# avr-remocon.net
KiCad netlist of a schematic drawn in EAGLE
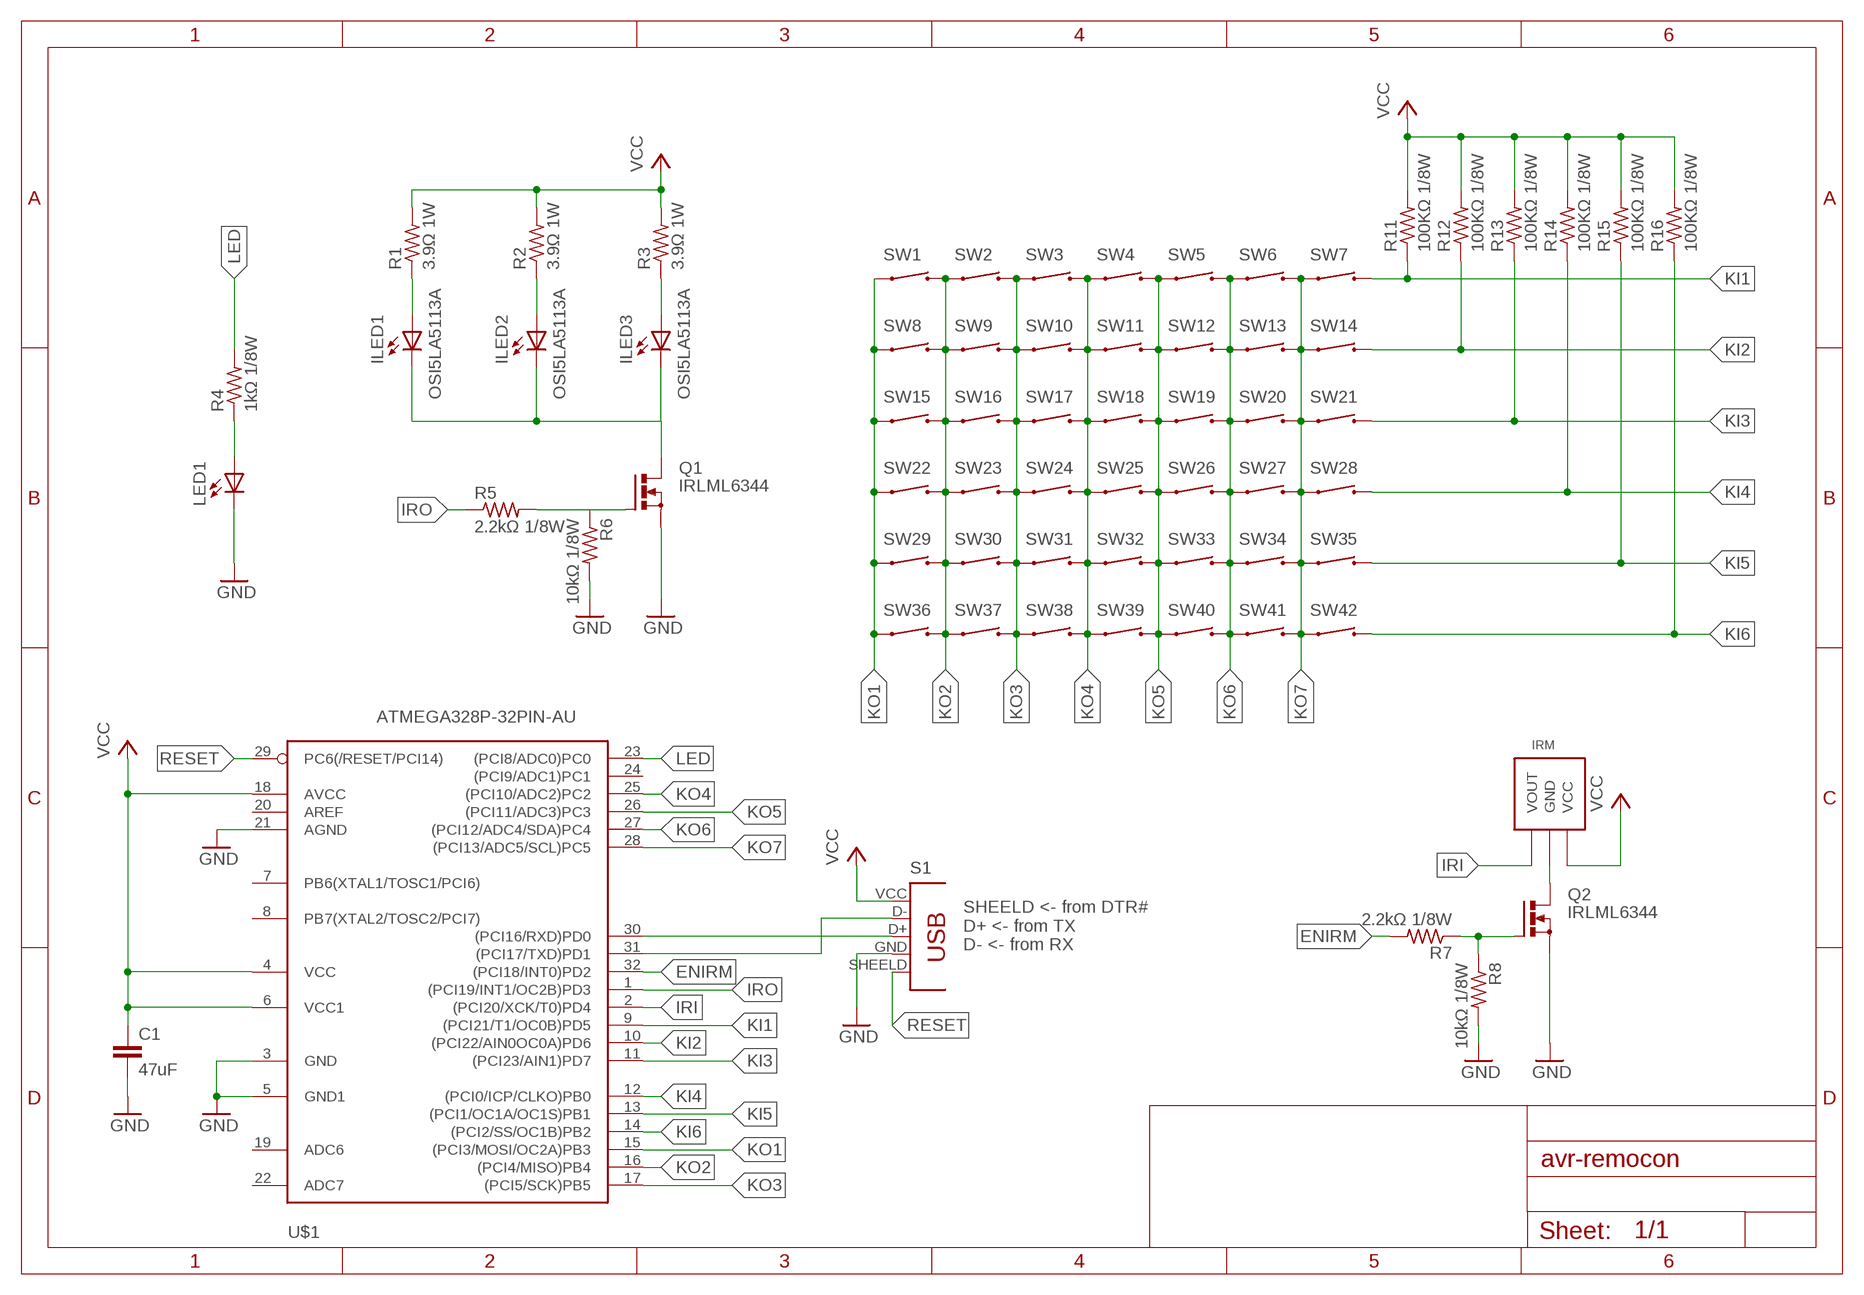
[diagram p0: schematic, sheet 1]

(export (version "E")
  (design (tool "Eeschema 10.0.6"))
  (components
    (comp (ref "C1")
      (value "47uF")
      (footprint "eagle-import:C3216")
      (libsource (lib "eagle-import") (part "C-EUC3216"))
    )
    (comp (ref "ILED1")
      (value "OSI5LA5113A")
      (footprint "eagle-import:LED5MM-SIDE-DOWN3")
      (libsource (lib "eagle-import") (part "LED-SIDEDOWN3"))
    )
    (comp (ref "ILED2")
      (value "OSI5LA5113A")
      (footprint "eagle-import:LED5MM-SIDE-DOWN3")
      (libsource (lib "eagle-import") (part "LED-SIDEDOWN3"))
    )
    (comp (ref "ILED3")
      (value "OSI5LA5113A")
      (footprint "eagle-import:LED5MM-SIDE-DOWN3")
      (libsource (lib "eagle-import") (part "LED-SIDEDOWN3"))
    )
    (comp (ref "IRM")
      (value "IRM2161")
      (footprint "eagle-import:IRM2161")
      (libsource (lib "eagle-import") (part "IRM2161"))
    )
    (comp (ref "LED1")
      (value "LG_T679-E1F1-1")
      (footprint "eagle-import:PLCC2")
      (libsource (lib "eagle-import") (part "_T679-?-1E1F1LG"))
    )
    (comp (ref "Q1")
      (value "IRLML6344")
      (footprint "eagle-import:SOT-23")
      (libsource (lib "eagle-import") (part "IRLML6344"))
    )
    (comp (ref "Q2")
      (value "IRLML6344")
      (footprint "eagle-import:SOT-23")
      (libsource (lib "eagle-import") (part "IRLML6344"))
    )
    (comp (ref "R1")
      (value "3.9Ω 1W")
      (footprint "eagle-import:R2512W")
      (libsource (lib "eagle-import") (part "rcl_334_R-US_R2512W"))
    )
    (comp (ref "R2")
      (value "3.9Ω 1W")
      (footprint "eagle-import:R2512W")
      (libsource (lib "eagle-import") (part "rcl_334_R-US_R2512W"))
    )
    (comp (ref "R3")
      (value "3.9Ω 1W")
      (footprint "eagle-import:R2512W")
      (libsource (lib "eagle-import") (part "R-US_R2512W"))
    )
    (comp (ref "R4")
      (value "1kΩ 1/8W")
      (footprint "eagle-import:R0805")
      (libsource (lib "eagle-import") (part "R-US_R0805"))
    )
    (comp (ref "R5")
      (value "2.2kΩ 1/8W")
      (footprint "eagle-import:R0805")
      (libsource (lib "eagle-import") (part "R-US_R0805"))
    )
    (comp (ref "R6")
      (value "10kΩ 1/8W")
      (footprint "eagle-import:R0805")
      (libsource (lib "eagle-import") (part "R-US_R0805"))
    )
    (comp (ref "R7")
      (value "2.2kΩ 1/8W")
      (footprint "eagle-import:R0805")
      (libsource (lib "eagle-import") (part "rcl_334_R-US_R0805"))
    )
    (comp (ref "R8")
      (value "10kΩ 1/8W")
      (footprint "eagle-import:R0805")
      (libsource (lib "eagle-import") (part "rcl_334_R-US_R0805"))
    )
    (comp (ref "R11")
      (value "100KΩ 1/8W")
      (footprint "eagle-import:R0805")
      (libsource (lib "eagle-import") (part "R-US_R0805"))
    )
    (comp (ref "R12")
      (value "100KΩ 1/8W")
      (footprint "eagle-import:R0805")
      (libsource (lib "eagle-import") (part "R-US_R0805"))
    )
    (comp (ref "R13")
      (value "100KΩ 1/8W")
      (footprint "eagle-import:R0805")
      (libsource (lib "eagle-import") (part "R-US_R0805"))
    )
    (comp (ref "R14")
      (value "100KΩ 1/8W")
      (footprint "eagle-import:R0805")
      (libsource (lib "eagle-import") (part "R-US_R0805"))
    )
    (comp (ref "R15")
      (value "100KΩ 1/8W")
      (footprint "eagle-import:R0805")
      (libsource (lib "eagle-import") (part "R-US_R0805"))
    )
    (comp (ref "R16")
      (value "100KΩ 1/8W")
      (footprint "eagle-import:R0805")
      (libsource (lib "eagle-import") (part "R-US_R0805"))
    )
    (comp (ref "S1")
      (value "TYPE-A+SHILED-MALE")
      (footprint "eagle-import:TYPE-A-MALE")
      (libsource (lib "eagle-import") (part "TYPE-A+SHILED-MALE"))
    )
    (comp (ref "SW1")
      (value "RUBBER-SWITCH")
      (footprint "eagle-import:HALF-PITCH")
      (libsource (lib "eagle-import") (part "RUBBER-SWITCH"))
    )
    (comp (ref "SW2")
      (value "RUBBER-SWITCH")
      (footprint "eagle-import:HALF-PITCH")
      (libsource (lib "eagle-import") (part "RUBBER-SWITCH"))
    )
    (comp (ref "SW3")
      (value "RUBBER-SWITCH")
      (footprint "eagle-import:HALF-PITCH")
      (libsource (lib "eagle-import") (part "RUBBER-SWITCH"))
    )
    (comp (ref "SW4")
      (value "RUBBER-SWITCH")
      (footprint "eagle-import:HALF-PITCH")
      (libsource (lib "eagle-import") (part "RUBBER-SWITCH"))
    )
    (comp (ref "SW5")
      (value "RUBBER-SWITCH")
      (footprint "eagle-import:HALF-PITCH")
      (libsource (lib "eagle-import") (part "RUBBER-SWITCH"))
    )
    (comp (ref "SW6")
      (value "RUBBER-SWITCH")
      (footprint "eagle-import:HALF-PITCH")
      (libsource (lib "eagle-import") (part "RUBBER-SWITCH"))
    )
    (comp (ref "SW7")
      (value "RUBBER-SWITCH")
      (footprint "eagle-import:HALF-PITCH")
      (libsource (lib "eagle-import") (part "RUBBER-SWITCH"))
    )
    (comp (ref "SW8")
      (value "RUBBER-SWITCH")
      (footprint "eagle-import:HALF-PITCH")
      (libsource (lib "eagle-import") (part "RUBBER-SWITCH"))
    )
    (comp (ref "SW9")
      (value "RUBBER-SWITCH")
      (footprint "eagle-import:HALF-PITCH")
      (libsource (lib "eagle-import") (part "RUBBER-SWITCH"))
    )
    (comp (ref "SW10")
      (value "RUBBER-SWITCH")
      (footprint "eagle-import:HALF-PITCH")
      (libsource (lib "eagle-import") (part "RUBBER-SWITCH"))
    )
    (comp (ref "SW11")
      (value "RUBBER-SWITCH")
      (footprint "eagle-import:HALF-PITCH")
      (libsource (lib "eagle-import") (part "RUBBER-SWITCH"))
    )
    (comp (ref "SW12")
      (value "RUBBER-SWITCH")
      (footprint "eagle-import:HALF-PITCH")
      (libsource (lib "eagle-import") (part "RUBBER-SWITCH"))
    )
    (comp (ref "SW13")
      (value "RUBBER-SWITCH")
      (footprint "eagle-import:HALF-PITCH")
      (libsource (lib "eagle-import") (part "RUBBER-SWITCH"))
    )
    (comp (ref "SW14")
      (value "RUBBER-SWITCH")
      (footprint "eagle-import:HALF-PITCH")
      (libsource (lib "eagle-import") (part "RUBBER-SWITCH"))
    )
    (comp (ref "SW15")
      (value "RUBBER-SWITCH")
      (footprint "eagle-import:HALF-PITCH")
      (libsource (lib "eagle-import") (part "RUBBER-SWITCH"))
    )
    (comp (ref "SW16")
      (value "RUBBER-SWITCH")
      (footprint "eagle-import:HALF-PITCH")
      (libsource (lib "eagle-import") (part "RUBBER-SWITCH"))
    )
    (comp (ref "SW17")
      (value "RUBBER-SWITCH")
      (footprint "eagle-import:HALF-PITCH")
      (libsource (lib "eagle-import") (part "RUBBER-SWITCH"))
    )
    (comp (ref "SW18")
      (value "RUBBER-SWITCH")
      (footprint "eagle-import:HALF-PITCH")
      (libsource (lib "eagle-import") (part "RUBBER-SWITCH"))
    )
    (comp (ref "SW19")
      (value "RUBBER-SWITCH")
      (footprint "eagle-import:HALF-PITCH")
      (libsource (lib "eagle-import") (part "RUBBER-SWITCH"))
    )
    (comp (ref "SW20")
      (value "RUBBER-SWITCH")
      (footprint "eagle-import:HALF-PITCH")
      (libsource (lib "eagle-import") (part "RUBBER-SWITCH"))
    )
    (comp (ref "SW21")
      (value "RUBBER-SWITCH")
      (footprint "eagle-import:HALF-PITCH")
      (libsource (lib "eagle-import") (part "RUBBER-SWITCH"))
    )
    (comp (ref "SW22")
      (value "RUBBER-SWITCH")
      (footprint "eagle-import:HALF-PITCH")
      (libsource (lib "eagle-import") (part "RUBBER-SWITCH"))
    )
    (comp (ref "SW23")
      (value "RUBBER-SWITCH")
      (footprint "eagle-import:HALF-PITCH")
      (libsource (lib "eagle-import") (part "RUBBER-SWITCH"))
    )
    (comp (ref "SW24")
      (value "RUBBER-SWITCH")
      (footprint "eagle-import:HALF-PITCH")
      (libsource (lib "eagle-import") (part "RUBBER-SWITCH"))
    )
    (comp (ref "SW25")
      (value "RUBBER-SWITCH")
      (footprint "eagle-import:HALF-PITCH")
      (libsource (lib "eagle-import") (part "RUBBER-SWITCH"))
    )
    (comp (ref "SW26")
      (value "RUBBER-SWITCH")
      (footprint "eagle-import:HALF-PITCH")
      (libsource (lib "eagle-import") (part "RUBBER-SWITCH"))
    )
    (comp (ref "SW27")
      (value "RUBBER-SWITCH")
      (footprint "eagle-import:HALF-PITCH")
      (libsource (lib "eagle-import") (part "RUBBER-SWITCH"))
    )
    (comp (ref "SW28")
      (value "RUBBER-SWITCH")
      (footprint "eagle-import:HALF-PITCH")
      (libsource (lib "eagle-import") (part "RUBBER-SWITCH"))
    )
    (comp (ref "SW29")
      (value "RUBBER-SWITCH")
      (footprint "eagle-import:HALF-PITCH")
      (libsource (lib "eagle-import") (part "RUBBER-SWITCH"))
    )
    (comp (ref "SW30")
      (value "RUBBER-SWITCH")
      (footprint "eagle-import:HALF-PITCH")
      (libsource (lib "eagle-import") (part "RUBBER-SWITCH"))
    )
    (comp (ref "SW31")
      (value "RUBBER-SWITCH")
      (footprint "eagle-import:HALF-PITCH")
      (libsource (lib "eagle-import") (part "RUBBER-SWITCH"))
    )
    (comp (ref "SW32")
      (value "RUBBER-SWITCH")
      (footprint "eagle-import:HALF-PITCH")
      (libsource (lib "eagle-import") (part "RUBBER-SWITCH"))
    )
    (comp (ref "SW33")
      (value "RUBBER-SWITCH")
      (footprint "eagle-import:HALF-PITCH")
      (libsource (lib "eagle-import") (part "RUBBER-SWITCH"))
    )
    (comp (ref "SW34")
      (value "RUBBER-SWITCH")
      (footprint "eagle-import:HALF-PITCH")
      (libsource (lib "eagle-import") (part "RUBBER-SWITCH"))
    )
    (comp (ref "SW35")
      (value "RUBBER-SWITCH")
      (footprint "eagle-import:HALF-PITCH")
      (libsource (lib "eagle-import") (part "RUBBER-SWITCH"))
    )
    (comp (ref "SW36")
      (value "RUBBER-SWITCH")
      (footprint "eagle-import:HALF-PITCH")
      (libsource (lib "eagle-import") (part "RUBBER-SWITCH"))
    )
    (comp (ref "SW37")
      (value "RUBBER-SWITCH")
      (footprint "eagle-import:HALF-PITCH")
      (libsource (lib "eagle-import") (part "RUBBER-SWITCH"))
    )
    (comp (ref "SW38")
      (value "RUBBER-SWITCH")
      (footprint "eagle-import:HALF-PITCH")
      (libsource (lib "eagle-import") (part "RUBBER-SWITCH"))
    )
    (comp (ref "SW39")
      (value "RUBBER-SWITCH")
      (footprint "eagle-import:HALF-PITCH")
      (libsource (lib "eagle-import") (part "RUBBER-SWITCH"))
    )
    (comp (ref "SW40")
      (value "RUBBER-SWITCH")
      (footprint "eagle-import:HALF-PITCH")
      (libsource (lib "eagle-import") (part "RUBBER-SWITCH"))
    )
    (comp (ref "SW41")
      (value "RUBBER-SWITCH")
      (footprint "eagle-import:HALF-PITCH")
      (libsource (lib "eagle-import") (part "RUBBER-SWITCH"))
    )
    (comp (ref "SW42")
      (value "RUBBER-SWITCH")
      (footprint "eagle-import:HALF-PITCH")
      (libsource (lib "eagle-import") (part "RUBBER-SWITCH"))
    )
    (comp (ref "U$1")
      (value "ATMEGA328P-32PIN-AU")
      (footprint "eagle-import:TQFP32-08")
      (libsource (lib "eagle-import") (part "ATMEGA328P-32PIN-AU"))
    )
  )
  (nets
    (net (code "1") (name "ENIRM") (class "Default")
      (node (ref "R7") (pin "2") (pinfunction "2_2") (pintype "passive"))
      (node (ref "U$1") (pin "32") (pinfunction "(PCI18/INT0)PD2_32") (pintype "bidirectional"))
    )
    (net (code "2") (name "GND") (class "Default")
      (node (ref "C1") (pin "2") (pinfunction "2_2") (pintype "passive"))
      (node (ref "LED1") (pin "C") (pinfunction "C_C") (pintype "passive"))
      (node (ref "Q1") (pin "P2") (pinfunction "S_P2") (pintype "passive"))
      (node (ref "Q2") (pin "P2") (pinfunction "S_P2") (pintype "passive"))
      (node (ref "R6") (pin "2") (pinfunction "2_2") (pintype "passive"))
      (node (ref "R8") (pin "2") (pinfunction "2_2") (pintype "passive"))
      (node (ref "S1") (pin "GND") (pinfunction "4_GND") (pintype "power_in"))
      (node (ref "U$1") (pin "21") (pinfunction "AGND_21") (pintype "bidirectional"))
      (node (ref "U$1") (pin "3") (pinfunction "GND_3") (pintype "bidirectional"))
      (node (ref "U$1") (pin "5") (pinfunction "GND1_5") (pintype "bidirectional"))
    )
    (net (code "3") (name "IRI") (class "Default")
      (node (ref "IRM") (pin "P$1") (pinfunction "VOUT_P$1") (pintype "bidirectional"))
      (node (ref "U$1") (pin "2") (pinfunction "(PCI20/XCK/T0)PD4_2") (pintype "bidirectional"))
    )
    (net (code "4") (name "IRO") (class "Default")
      (node (ref "R5") (pin "1") (pinfunction "1_1") (pintype "passive"))
      (node (ref "U$1") (pin "1") (pinfunction "(PCI19/INT1/OC2B)PD3_1") (pintype "bidirectional"))
    )
    (net (code "5") (name "KI1") (class "Default")
      (node (ref "R11") (pin "1") (pinfunction "1_1") (pintype "passive"))
      (node (ref "SW7") (pin "P2") (pinfunction "2_P2") (pintype "passive"))
      (node (ref "U$1") (pin "9") (pinfunction "(PCI21/T1/OC0B)PD5_9") (pintype "bidirectional"))
    )
    (net (code "6") (name "KI2") (class "Default")
      (node (ref "R12") (pin "1") (pinfunction "1_1") (pintype "passive"))
      (node (ref "SW14") (pin "P2") (pinfunction "2_P2") (pintype "passive"))
      (node (ref "U$1") (pin "10") (pinfunction "(PCI22/AIN0OC0A)PD6_10") (pintype "bidirectional"))
    )
    (net (code "7") (name "KI3") (class "Default")
      (node (ref "R13") (pin "1") (pinfunction "1_1") (pintype "passive"))
      (node (ref "SW21") (pin "P2") (pinfunction "2_P2") (pintype "passive"))
      (node (ref "U$1") (pin "11") (pinfunction "(PCI23/AIN1)PD7_11") (pintype "bidirectional"))
    )
    (net (code "8") (name "KI4") (class "Default")
      (node (ref "R14") (pin "1") (pinfunction "1_1") (pintype "passive"))
      (node (ref "SW28") (pin "P2") (pinfunction "2_P2") (pintype "passive"))
      (node (ref "U$1") (pin "12") (pinfunction "(PCI0/ICP/CLKO)PB0_12") (pintype "bidirectional"))
    )
    (net (code "9") (name "KI5") (class "Default")
      (node (ref "R15") (pin "1") (pinfunction "1_1") (pintype "passive"))
      (node (ref "SW35") (pin "P2") (pinfunction "2_P2") (pintype "passive"))
      (node (ref "U$1") (pin "13") (pinfunction "(PCI1/OC1A/OC1S)PB1_13") (pintype "bidirectional"))
    )
    (net (code "10") (name "KI6") (class "Default")
      (node (ref "R16") (pin "1") (pinfunction "1_1") (pintype "passive"))
      (node (ref "SW42") (pin "P2") (pinfunction "2_P2") (pintype "passive"))
      (node (ref "U$1") (pin "14") (pinfunction "(PCI2/SS/OC1B)PB2_14") (pintype "bidirectional"))
    )
    (net (code "11") (name "KO1") (class "Default")
      (node (ref "SW1") (pin "P1") (pinfunction "1_P1") (pintype "passive"))
      (node (ref "SW15") (pin "P1") (pinfunction "1_P1") (pintype "passive"))
      (node (ref "SW22") (pin "P1") (pinfunction "1_P1") (pintype "passive"))
      (node (ref "SW29") (pin "P1") (pinfunction "1_P1") (pintype "passive"))
      (node (ref "SW36") (pin "P1") (pinfunction "1_P1") (pintype "passive"))
      (node (ref "SW8") (pin "P1") (pinfunction "1_P1") (pintype "passive"))
      (node (ref "U$1") (pin "15") (pinfunction "(PCI3/MOSI/OC2A)PB3_15") (pintype "bidirectional"))
    )
    (net (code "12") (name "KO2") (class "Default")
      (node (ref "SW1") (pin "P2") (pinfunction "2_P2") (pintype "passive"))
      (node (ref "SW15") (pin "P2") (pinfunction "2_P2") (pintype "passive"))
      (node (ref "SW16") (pin "P1") (pinfunction "1_P1") (pintype "passive"))
      (node (ref "SW2") (pin "P1") (pinfunction "1_P1") (pintype "passive"))
      (node (ref "SW22") (pin "P2") (pinfunction "2_P2") (pintype "passive"))
      (node (ref "SW23") (pin "P1") (pinfunction "1_P1") (pintype "passive"))
      (node (ref "SW29") (pin "P2") (pinfunction "2_P2") (pintype "passive"))
      (node (ref "SW30") (pin "P1") (pinfunction "1_P1") (pintype "passive"))
      (node (ref "SW36") (pin "P2") (pinfunction "2_P2") (pintype "passive"))
      (node (ref "SW37") (pin "P1") (pinfunction "1_P1") (pintype "passive"))
      (node (ref "SW8") (pin "P2") (pinfunction "2_P2") (pintype "passive"))
      (node (ref "SW9") (pin "P1") (pinfunction "1_P1") (pintype "passive"))
      (node (ref "U$1") (pin "16") (pinfunction "(PCI4/MISO)PB4_16") (pintype "bidirectional"))
    )
    (net (code "13") (name "KO3") (class "Default")
      (node (ref "SW10") (pin "P1") (pinfunction "1_P1") (pintype "passive"))
      (node (ref "SW16") (pin "P2") (pinfunction "2_P2") (pintype "passive"))
      (node (ref "SW17") (pin "P1") (pinfunction "1_P1") (pintype "passive"))
      (node (ref "SW2") (pin "P2") (pinfunction "2_P2") (pintype "passive"))
      (node (ref "SW23") (pin "P2") (pinfunction "2_P2") (pintype "passive"))
      (node (ref "SW24") (pin "P1") (pinfunction "1_P1") (pintype "passive"))
      (node (ref "SW3") (pin "P1") (pinfunction "1_P1") (pintype "passive"))
      (node (ref "SW30") (pin "P2") (pinfunction "2_P2") (pintype "passive"))
      (node (ref "SW31") (pin "P1") (pinfunction "1_P1") (pintype "passive"))
      (node (ref "SW37") (pin "P2") (pinfunction "2_P2") (pintype "passive"))
      (node (ref "SW38") (pin "P1") (pinfunction "1_P1") (pintype "passive"))
      (node (ref "SW9") (pin "P2") (pinfunction "2_P2") (pintype "passive"))
      (node (ref "U$1") (pin "17") (pinfunction "(PCI5/SCK)PB5_17") (pintype "bidirectional"))
    )
    (net (code "14") (name "KO4") (class "Default")
      (node (ref "SW10") (pin "P2") (pinfunction "2_P2") (pintype "passive"))
      (node (ref "SW11") (pin "P1") (pinfunction "1_P1") (pintype "passive"))
      (node (ref "SW17") (pin "P2") (pinfunction "2_P2") (pintype "passive"))
      (node (ref "SW18") (pin "P1") (pinfunction "1_P1") (pintype "passive"))
      (node (ref "SW24") (pin "P2") (pinfunction "2_P2") (pintype "passive"))
      (node (ref "SW25") (pin "P1") (pinfunction "1_P1") (pintype "passive"))
      (node (ref "SW3") (pin "P2") (pinfunction "2_P2") (pintype "passive"))
      (node (ref "SW31") (pin "P2") (pinfunction "2_P2") (pintype "passive"))
      (node (ref "SW32") (pin "P1") (pinfunction "1_P1") (pintype "passive"))
      (node (ref "SW38") (pin "P2") (pinfunction "2_P2") (pintype "passive"))
      (node (ref "SW39") (pin "P1") (pinfunction "1_P1") (pintype "passive"))
      (node (ref "SW4") (pin "P1") (pinfunction "1_P1") (pintype "passive"))
      (node (ref "U$1") (pin "25") (pinfunction "(PCI10/ADC2)PC2_25") (pintype "bidirectional"))
    )
    (net (code "15") (name "KO5") (class "Default")
      (node (ref "SW11") (pin "P2") (pinfunction "2_P2") (pintype "passive"))
      (node (ref "SW12") (pin "P1") (pinfunction "1_P1") (pintype "passive"))
      (node (ref "SW18") (pin "P2") (pinfunction "2_P2") (pintype "passive"))
      (node (ref "SW19") (pin "P1") (pinfunction "1_P1") (pintype "passive"))
      (node (ref "SW25") (pin "P2") (pinfunction "2_P2") (pintype "passive"))
      (node (ref "SW26") (pin "P1") (pinfunction "1_P1") (pintype "passive"))
      (node (ref "SW32") (pin "P2") (pinfunction "2_P2") (pintype "passive"))
      (node (ref "SW33") (pin "P1") (pinfunction "1_P1") (pintype "passive"))
      (node (ref "SW39") (pin "P2") (pinfunction "2_P2") (pintype "passive"))
      (node (ref "SW4") (pin "P2") (pinfunction "2_P2") (pintype "passive"))
      (node (ref "SW40") (pin "P1") (pinfunction "1_P1") (pintype "passive"))
      (node (ref "SW5") (pin "P1") (pinfunction "1_P1") (pintype "passive"))
      (node (ref "U$1") (pin "26") (pinfunction "(PCI11/ADC3)PC3_26") (pintype "bidirectional"))
    )
    (net (code "16") (name "KO6") (class "Default")
      (node (ref "SW12") (pin "P2") (pinfunction "2_P2") (pintype "passive"))
      (node (ref "SW13") (pin "P1") (pinfunction "1_P1") (pintype "passive"))
      (node (ref "SW19") (pin "P2") (pinfunction "2_P2") (pintype "passive"))
      (node (ref "SW20") (pin "P1") (pinfunction "1_P1") (pintype "passive"))
      (node (ref "SW26") (pin "P2") (pinfunction "2_P2") (pintype "passive"))
      (node (ref "SW27") (pin "P1") (pinfunction "1_P1") (pintype "passive"))
      (node (ref "SW33") (pin "P2") (pinfunction "2_P2") (pintype "passive"))
      (node (ref "SW34") (pin "P1") (pinfunction "1_P1") (pintype "passive"))
      (node (ref "SW40") (pin "P2") (pinfunction "2_P2") (pintype "passive"))
      (node (ref "SW41") (pin "P1") (pinfunction "1_P1") (pintype "passive"))
      (node (ref "SW5") (pin "P2") (pinfunction "2_P2") (pintype "passive"))
      (node (ref "SW6") (pin "P1") (pinfunction "1_P1") (pintype "passive"))
      (node (ref "U$1") (pin "27") (pinfunction "(PCI12/ADC4/SDA)PC4_27") (pintype "bidirectional"))
    )
    (net (code "17") (name "KO7") (class "Default")
      (node (ref "SW13") (pin "P2") (pinfunction "2_P2") (pintype "passive"))
      (node (ref "SW14") (pin "P1") (pinfunction "1_P1") (pintype "passive"))
      (node (ref "SW20") (pin "P2") (pinfunction "2_P2") (pintype "passive"))
      (node (ref "SW21") (pin "P1") (pinfunction "1_P1") (pintype "passive"))
      (node (ref "SW27") (pin "P2") (pinfunction "2_P2") (pintype "passive"))
      (node (ref "SW28") (pin "P1") (pinfunction "1_P1") (pintype "passive"))
      (node (ref "SW34") (pin "P2") (pinfunction "2_P2") (pintype "passive"))
      (node (ref "SW35") (pin "P1") (pinfunction "1_P1") (pintype "passive"))
      (node (ref "SW41") (pin "P2") (pinfunction "2_P2") (pintype "passive"))
      (node (ref "SW42") (pin "P1") (pinfunction "1_P1") (pintype "passive"))
      (node (ref "SW6") (pin "P2") (pinfunction "2_P2") (pintype "passive"))
      (node (ref "SW7") (pin "P1") (pinfunction "1_P1") (pintype "passive"))
      (node (ref "U$1") (pin "28") (pinfunction "(PCI13/ADC5/SCL)PC5_28") (pintype "bidirectional"))
    )
    (net (code "18") (name "LED") (class "Default")
      (node (ref "R4") (pin "2") (pinfunction "2_2") (pintype "passive"))
      (node (ref "U$1") (pin "23") (pinfunction "(PCI8/ADC0)PC0_23") (pintype "bidirectional"))
    )
    (net (code "19") (name "Net-(ILED1-C)") (class "Default")
      (node (ref "ILED1") (pin "K") (pinfunction "C_K") (pintype "passive"))
      (node (ref "ILED2") (pin "K") (pinfunction "C_K") (pintype "passive"))
      (node (ref "ILED3") (pin "K") (pinfunction "C_K") (pintype "passive"))
      (node (ref "Q1") (pin "P3") (pinfunction "D_P3") (pintype "passive"))
    )
    (net (code "20") (name "Net-(ILED1-PadA)") (class "Default")
      (node (ref "ILED1") (pin "A") (pinfunction "A_A") (pintype "passive"))
      (node (ref "R1") (pin "1") (pinfunction "1_1") (pintype "passive"))
    )
    (net (code "21") (name "Net-(ILED2-PadA)") (class "Default")
      (node (ref "ILED2") (pin "A") (pinfunction "A_A") (pintype "passive"))
      (node (ref "R2") (pin "1") (pinfunction "1_1") (pintype "passive"))
    )
    (net (code "22") (name "Net-(ILED3-PadA)") (class "Default")
      (node (ref "ILED3") (pin "A") (pinfunction "A_A") (pintype "passive"))
      (node (ref "R3") (pin "1") (pinfunction "1_1") (pintype "passive"))
    )
    (net (code "23") (name "Net-(IRM-GND)") (class "Default")
      (node (ref "IRM") (pin "P$2") (pinfunction "GND_P$2") (pintype "power_in"))
      (node (ref "Q2") (pin "P3") (pinfunction "D_P3") (pintype "passive"))
    )
    (net (code "24") (name "Net-(LED1-PadA)") (class "Default")
      (node (ref "LED1") (pin "A") (pinfunction "A_A") (pintype "passive"))
      (node (ref "R4") (pin "1") (pinfunction "1_1") (pintype "passive"))
    )
    (net (code "25") (name "Net-(Q1-G)") (class "Default")
      (node (ref "Q1") (pin "P1") (pinfunction "G_P1") (pintype "passive"))
      (node (ref "R5") (pin "2") (pinfunction "2_2") (pintype "passive"))
      (node (ref "R6") (pin "1") (pinfunction "1_1") (pintype "passive"))
    )
    (net (code "26") (name "Net-(Q2-G)") (class "Default")
      (node (ref "Q2") (pin "P1") (pinfunction "G_P1") (pintype "passive"))
      (node (ref "R7") (pin "1") (pinfunction "1_1") (pintype "passive"))
      (node (ref "R8") (pin "1") (pinfunction "1_1") (pintype "passive"))
    )
    (net (code "27") (name "Net-(S1-2)") (class "Default")
      (node (ref "S1") (pin "D-") (pinfunction "2_D-") (pintype "passive"))
      (node (ref "U$1") (pin "31") (pinfunction "(PCI17/TXD)PD1_31") (pintype "bidirectional"))
    )
    (net (code "28") (name "Net-(S1-3)") (class "Default")
      (node (ref "S1") (pin "D+") (pinfunction "3_D+") (pintype "passive"))
      (node (ref "U$1") (pin "30") (pinfunction "(PCI16/RXD)PD0_30") (pintype "bidirectional"))
    )
    (net (code "29") (name "RESET") (class "Default")
      (node (ref "S1") (pin "SHEELD") (pinfunction "5_SHEELD") (pintype "passive"))
      (node (ref "U$1") (pin "29") (pinfunction "PC6(/RESET/PCI14)_29") (pintype "bidirectional"))
    )
    (net (code "30") (name "VCC") (class "Default")
      (node (ref "C1") (pin "1") (pinfunction "1_1") (pintype "passive"))
      (node (ref "IRM") (pin "P$3") (pinfunction "VCC_P$3") (pintype "power_in"))
      (node (ref "R1") (pin "2") (pinfunction "2_2") (pintype "passive"))
      (node (ref "R11") (pin "2") (pinfunction "2_2") (pintype "passive"))
      (node (ref "R12") (pin "2") (pinfunction "2_2") (pintype "passive"))
      (node (ref "R13") (pin "2") (pinfunction "2_2") (pintype "passive"))
      (node (ref "R14") (pin "2") (pinfunction "2_2") (pintype "passive"))
      (node (ref "R15") (pin "2") (pinfunction "2_2") (pintype "passive"))
      (node (ref "R16") (pin "2") (pinfunction "2_2") (pintype "passive"))
      (node (ref "R2") (pin "2") (pinfunction "2_2") (pintype "passive"))
      (node (ref "R3") (pin "2") (pinfunction "2_2") (pintype "passive"))
      (node (ref "S1") (pin "VCC") (pinfunction "1_VCC") (pintype "power_in"))
      (node (ref "U$1") (pin "18") (pinfunction "AVCC_18") (pintype "bidirectional"))
      (node (ref "U$1") (pin "4") (pinfunction "VCC_4") (pintype "bidirectional"))
      (node (ref "U$1") (pin "6") (pinfunction "VCC1_6") (pintype "bidirectional"))
    )
    (net (code "31") (name "unconnected-(U$1-(PCI9{slash}ADC1)PC1-Pad24)") (class "Default")
      (node (ref "U$1") (pin "24") (pinfunction "(PCI9/ADC1)PC1_24") (pintype "bidirectional"))
    )
    (net (code "32") (name "unconnected-(U$1-ADC6-Pad19)") (class "Default")
      (node (ref "U$1") (pin "19") (pinfunction "ADC6_19") (pintype "bidirectional"))
    )
    (net (code "33") (name "unconnected-(U$1-ADC7-Pad22)") (class "Default")
      (node (ref "U$1") (pin "22") (pinfunction "ADC7_22") (pintype "bidirectional"))
    )
    (net (code "34") (name "unconnected-(U$1-AREF-Pad20)") (class "Default")
      (node (ref "U$1") (pin "20") (pinfunction "AREF_20") (pintype "bidirectional"))
    )
    (net (code "35") (name "unconnected-(U$1-PB6(XTAL1{slash}TOSC1{slash}PCI6)-Pad7)") (class "Default")
      (node (ref "U$1") (pin "7") (pinfunction "PB6(XTAL1/TOSC1/PCI6)_7") (pintype "bidirectional"))
    )
    (net (code "36") (name "unconnected-(U$1-PB7(XTAL2{slash}TOSC2{slash}PCI7)-Pad8)") (class "Default")
      (node (ref "U$1") (pin "8") (pinfunction "PB7(XTAL2/TOSC2/PCI7)_8") (pintype "bidirectional"))
    )
  )
)
